# 7segement2digits1badidea-mk-6_0.net
KiCad netlist of a schematic drawn in EAGLE
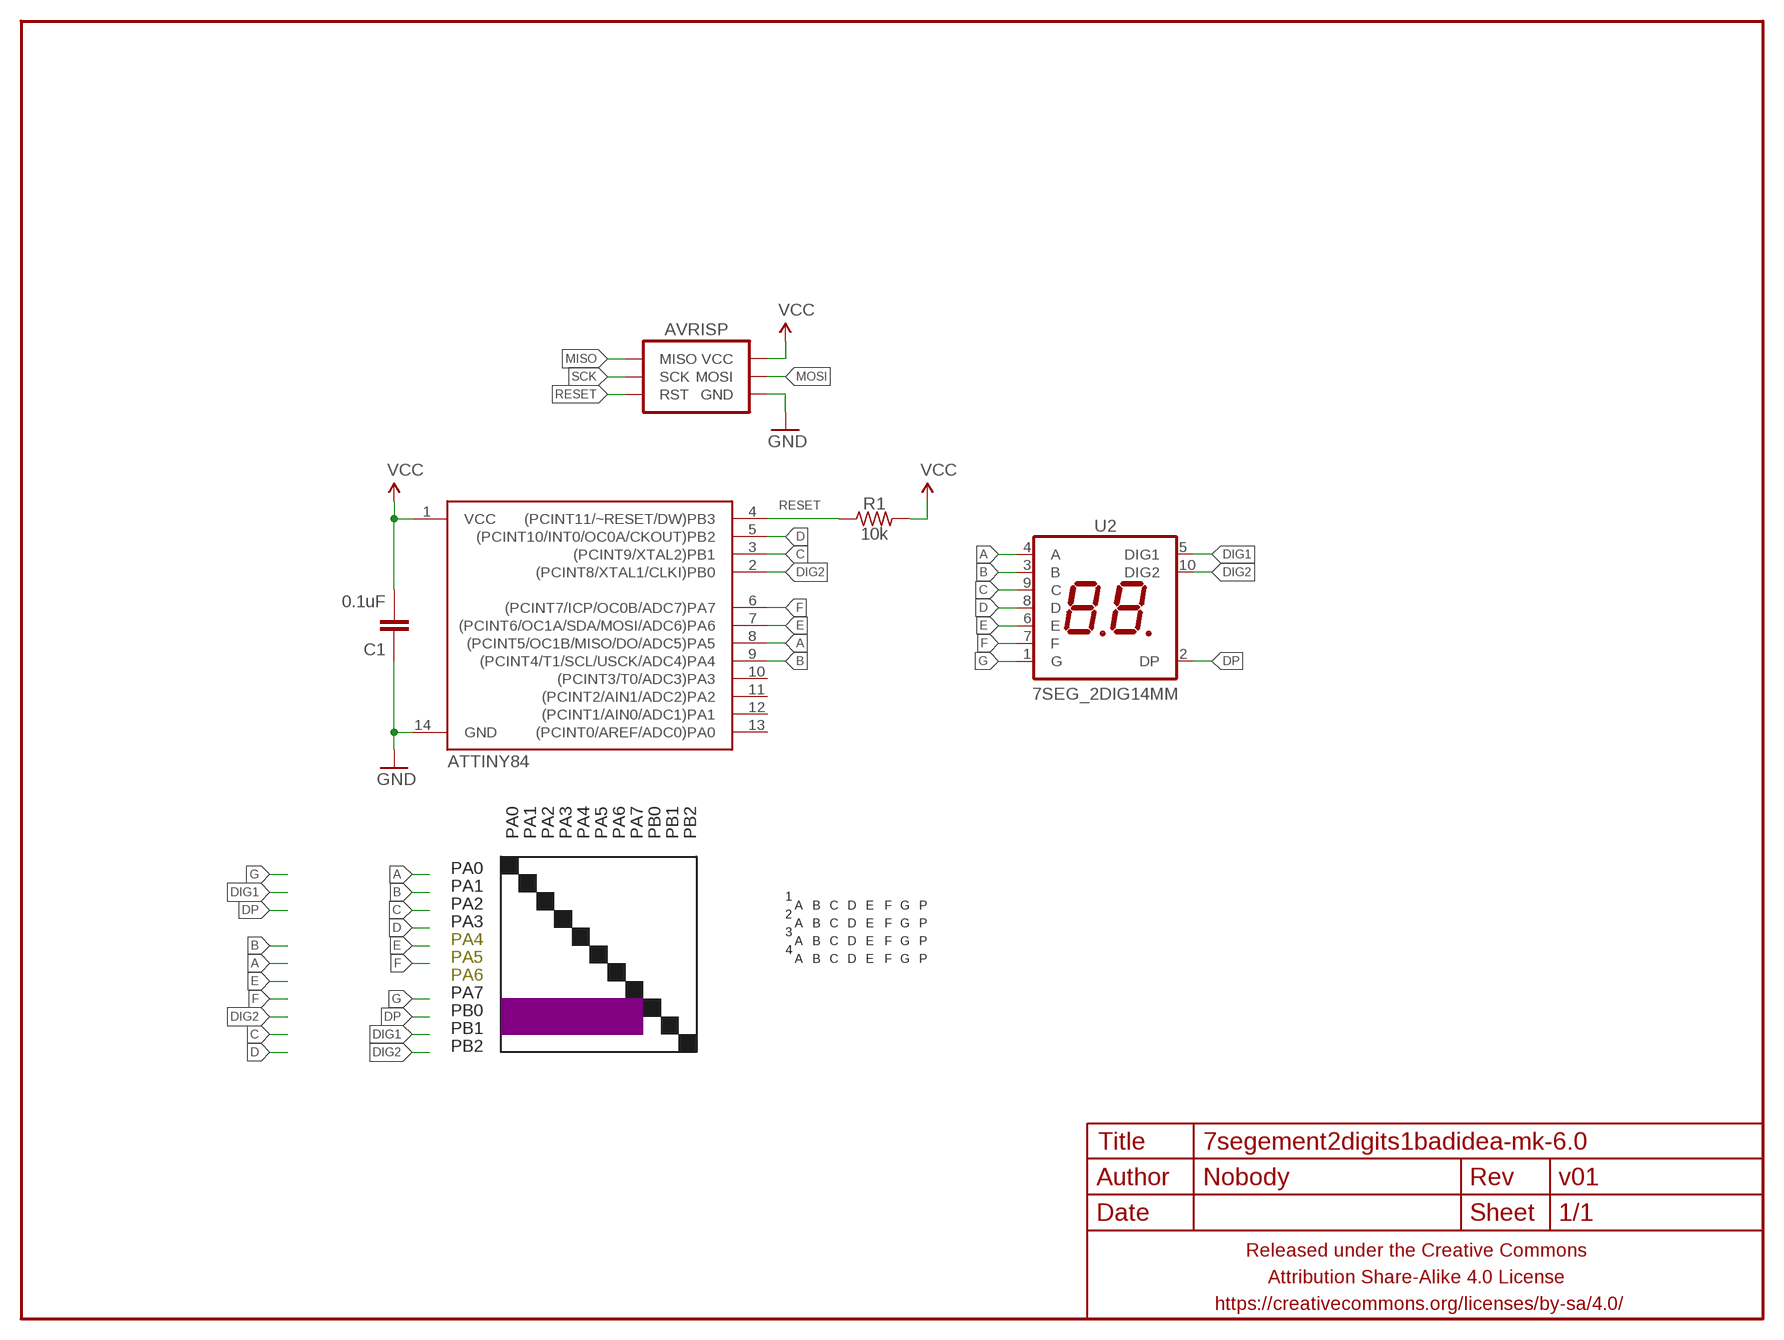
[diagram p0: schematic, sheet 1]

(export (version "E")
  (design (tool "Eeschema 10.0.6"))
  (components
    (comp (ref "AVRISP")
      (value "AVR_SPI_PRG_62X3_SMD")
      (footprint "eagle-import:2X3_SMD")
      (libsource (lib "eagle-import") (part "AVR_SPI_PRG_62X3_SMD"))
    )
    (comp (ref "C1")
      (value "0.1uF")
      (footprint "eagle-import:C0603")
      (libsource (lib "eagle-import") (part "CAPACITOR-CERAMICC0603"))
    )
    (comp (ref "FRAME1")
      (value "FRAME-LETTERNO_PACKAGE")
      (footprint "eagle-import:DUMMY")
      (fields (field (name "DESIGNER") "Nobody"))
      (libsource (lib "eagle-import") (part "FRAME-LETTERNO_PACKAGE"))
    )
    (comp (ref "R1")
      (value "10k")
      (footprint "eagle-import:R0603")
      (libsource (lib "eagle-import") (part "RESISTORR0603"))
    )
    (comp (ref "U1")
      (value "ATTINY84")
      (footprint "eagle-import:SO14")
      (libsource (lib "eagle-import") (part "ATTINY84"))
    )
    (comp (ref "U2")
      (value "7SEG_2DIG14MM")
      (footprint "eagle-import:7SEG_2DIG_14MM")
      (libsource (lib "eagle-import") (part "7SEG_2DIG14MM"))
    )
  )
  (nets
    (net (code "1") (name "A") (class "Default")
      (node (ref "U1") (pin "8") (pinfunction "(PCINT5/OC1B/MISO/DO/ADC5)PA5_8") (pintype "bidirectional"))
      (node (ref "U2") (pin "4") (pinfunction "A_4") (pintype "passive"))
    )
    (net (code "2") (name "B") (class "Default")
      (node (ref "U1") (pin "9") (pinfunction "(PCINT4/T1/SCL/USCK/ADC4)PA4_9") (pintype "bidirectional"))
      (node (ref "U2") (pin "3") (pinfunction "B_3") (pintype "passive"))
    )
    (net (code "3") (name "C") (class "Default")
      (node (ref "U1") (pin "3") (pinfunction "(PCINT9/XTAL2)PB1_3") (pintype "bidirectional"))
      (node (ref "U2") (pin "9") (pinfunction "C_9") (pintype "passive"))
    )
    (net (code "4") (name "D") (class "Default")
      (node (ref "U1") (pin "5") (pinfunction "(PCINT10/INT0/OC0A/CKOUT)PB2_5") (pintype "bidirectional"))
      (node (ref "U2") (pin "8") (pinfunction "D_8") (pintype "passive"))
    )
    (net (code "5") (name "DIG1") (class "Default")
      (node (ref "U2") (pin "5") (pinfunction "DIG1_5") (pintype "passive"))
    )
    (net (code "6") (name "DIG2") (class "Default")
      (node (ref "U1") (pin "2") (pinfunction "(PCINT8/XTAL1/CLKI)PB0_2") (pintype "bidirectional"))
      (node (ref "U2") (pin "10") (pinfunction "DIG2_10") (pintype "passive"))
    )
    (net (code "7") (name "DP") (class "Default")
      (node (ref "U2") (pin "2") (pinfunction "DP_2") (pintype "passive"))
    )
    (net (code "8") (name "E") (class "Default")
      (node (ref "U1") (pin "7") (pinfunction "(PCINT6/OC1A/SDA/MOSI/ADC6)PA6_7") (pintype "bidirectional"))
      (node (ref "U2") (pin "6") (pinfunction "E_6") (pintype "passive"))
    )
    (net (code "9") (name "F") (class "Default")
      (node (ref "U1") (pin "6") (pinfunction "(PCINT7/ICP/OC0B/ADC7)PA7_6") (pintype "bidirectional"))
      (node (ref "U2") (pin "7") (pinfunction "F_7") (pintype "passive"))
    )
    (net (code "10") (name "G") (class "Default")
      (node (ref "U2") (pin "1") (pinfunction "G_1") (pintype "passive"))
    )
    (net (code "11") (name "GND") (class "Default")
      (node (ref "AVRISP") (pin "6") (pinfunction "GND_6") (pintype "passive"))
      (node (ref "C1") (pin "1") (pinfunction "1_1") (pintype "passive"))
      (node (ref "U1") (pin "14") (pinfunction "GND_14") (pintype "bidirectional"))
    )
    (net (code "12") (name "MISO") (class "Default")
      (node (ref "AVRISP") (pin "1") (pinfunction "MISO_1") (pintype "passive"))
    )
    (net (code "13") (name "MOSI") (class "Default")
      (node (ref "AVRISP") (pin "4") (pinfunction "MOSI_4") (pintype "passive"))
    )
    (net (code "14") (name "RESET") (class "Default")
      (node (ref "AVRISP") (pin "5") (pinfunction "RST_5") (pintype "passive"))
      (node (ref "R1") (pin "1") (pinfunction "1_1") (pintype "passive"))
      (node (ref "U1") (pin "4") (pinfunction "(PCINT11/~{RESET/DW})PB3_4") (pintype "bidirectional"))
    )
    (net (code "15") (name "SCK") (class "Default")
      (node (ref "AVRISP") (pin "3") (pinfunction "SCK_3") (pintype "passive"))
    )
    (net (code "16") (name "VCC") (class "Default")
      (node (ref "AVRISP") (pin "2") (pinfunction "VCC_2") (pintype "passive"))
      (node (ref "C1") (pin "2") (pinfunction "2_2") (pintype "passive"))
      (node (ref "R1") (pin "2") (pinfunction "2_2") (pintype "passive"))
      (node (ref "U1") (pin "1") (pinfunction "VCC_1") (pintype "bidirectional"))
    )
    (net (code "17") (name "unconnected-(U1-(PCINT0{slash}AREF{slash}ADC0)PA0-Pad13)") (class "Default")
      (node (ref "U1") (pin "13") (pinfunction "(PCINT0/AREF/ADC0)PA0_13") (pintype "bidirectional"))
    )
    (net (code "18") (name "unconnected-(U1-(PCINT1{slash}AIN0{slash}ADC1)PA1-Pad12)") (class "Default")
      (node (ref "U1") (pin "12") (pinfunction "(PCINT1/AIN0/ADC1)PA1_12") (pintype "bidirectional"))
    )
    (net (code "19") (name "unconnected-(U1-(PCINT2{slash}AIN1{slash}ADC2)PA2-Pad11)") (class "Default")
      (node (ref "U1") (pin "11") (pinfunction "(PCINT2/AIN1/ADC2)PA2_11") (pintype "bidirectional"))
    )
    (net (code "20") (name "unconnected-(U1-(PCINT3{slash}T0{slash}ADC3)PA3-Pad10)") (class "Default")
      (node (ref "U1") (pin "10") (pinfunction "(PCINT3/T0/ADC3)PA3_10") (pintype "bidirectional"))
    )
  )
)
